# Sheet5.net
KiCad netlist of a schematic drawn in Altium Designer
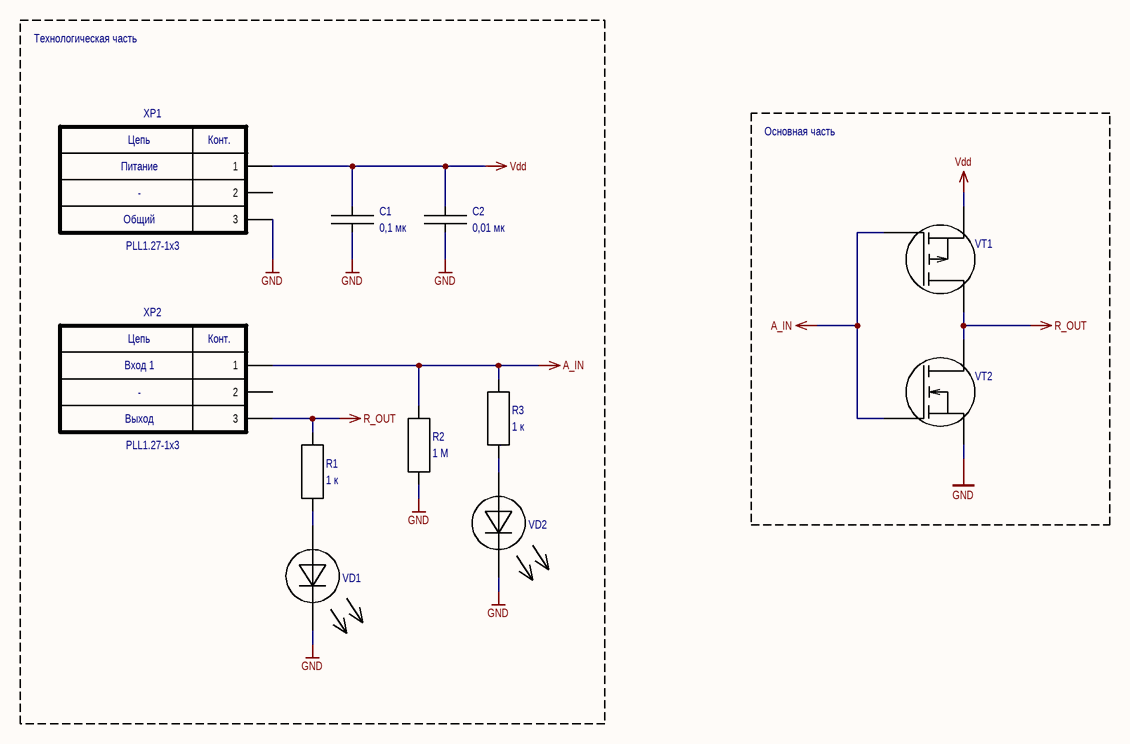
[diagram p0: Sheet5.SchDoc]

(export (version "E")
  (design (tool "Eeschema 10.0.6"))
  (components
    (comp (ref "C1")
      (value "0,1 мк")
      (footprint "K10-79_1.6_0.8(0603)")
      (fields (field (name "Comment") "0,1 мкФ ±* * * *, *"))
      (libsource (lib "IVT_LIB") (part "C - Конденсатор"))
    )
    (comp (ref "C2")
      (value "0,01 мк")
      (footprint "K10-79_1.6_0.8(0603)")
      (fields (field (name "Comment") "0,01 мкФ ±* * * *, *"))
      (libsource (lib "IVT_LIB") (part "C - Конденсатор"))
    )
    (comp (ref "R1")
      (value "1 к")
      (footprint "P1-12-0.1(0603)")
      (fields
        (field (name "PARTNUMBER") "RC0603JR-071KL")
        (field (name "TOLERANCE") "5 %")
        (field (name "Comment") "1 кОм ±5 % 0603, RC0603JR-071KL")
      )
      (libsource (lib "IVT_LIB") (part "R - Резистор"))
    )
    (comp (ref "R2")
      (value "1 М")
      (footprint "P1-12-0.1(0603)")
      (fields
        (field (name "PARTNUMBER") "RC0603JR-071KL")
        (field (name "TOLERANCE") "5 %")
        (field (name "Comment") "1 МОм ±5 % 0603, RC0603JR-071KL")
      )
      (libsource (lib "IVT_LIB") (part "R - Резистор"))
    )
    (comp (ref "R3")
      (value "1 к")
      (footprint "P1-12-0.1(0603)")
      (fields
        (field (name "PARTNUMBER") "RC0603JR-071KL")
        (field (name "TOLERANCE") "5 %")
        (field (name "Comment") "1 кОм ±5 % 0603, RC0603JR-071KL")
      )
      (libsource (lib "IVT_LIB") (part "R - Резистор"))
    )
    (comp (ref "VD1")
      (value "VD - Светодиод")
      (footprint "LED 0603")
      (fields (field (name "PARTNUMBER") "GNL-0805UBC-TL"))
      (libsource (lib "IVT_LIB") (part "VD - Светодиод"))
    )
    (comp (ref "VD2")
      (value "VD - Светодиод")
      (footprint "LED 0603")
      (fields (field (name "PARTNUMBER") "GNL-0805UBC-TL"))
      (libsource (lib "IVT_LIB") (part "VD - Светодиод"))
    )
    (comp (ref "VT1")
      (value "VT - Полевой транзистор P канал (MOSFET_P)")
      (footprint "SOT23(KT-46)")
      (description "VT")
      (libsource (lib "ALU") (part "VT - Полевой транзистор P канал (MOSFET_P)"))
    )
    (comp (ref "VT2")
      (value "VT - Полевой транзистор N канал (MOSFET_N)")
      (footprint "SOT23(KT-46)")
      (description "VT")
      (libsource (lib "ALU") (part "VT - Полевой транзистор N канал (MOSFET_N)"))
    )
    (comp (ref "XP1")
      (value "Вилка PLL1.27-1x3 RUICHI")
      (footprint "PCBComponent_1")
      (fields
        (field (name "1") "Питание")
        (field (name "3") "Общий")
        (field (name "2") "-")
        (field (name "PARTNUMBER") "PLL1.27-1x3")
      )
      (libsource (lib "IVT_LIB") (part "X - Контактное поле х3"))
    )
    (comp (ref "XP2")
      (value "KONT_POLE_POWER")
      (footprint "PCBComponent_1")
      (fields
        (field (name "1") "Вход 1")
        (field (name "2") "-")
        (field (name "3") "Выход")
        (field (name "PARTNUMBER") "PLL1.27-1x3")
      )
      (libsource (lib "IVT_LIB") (part "X - Контактное поле х3"))
    )
  )
  (nets
    (net (code "1") (name "A_IN") (class "Default")
      (node (ref "R2") (pin "1") (pinfunction "1_1") (pintype "passive"))
      (node (ref "R3") (pin "1") (pinfunction "1_1") (pintype "passive"))
      (node (ref "VT1") (pin "3") (pintype "passive"))
      (node (ref "VT2") (pin "3") (pintype "passive"))
      (node (ref "XP2") (pin "1") (pinfunction "1_1") (pintype "passive"))
    )
    (net (code "2") (name "GND") (class "Default")
      (node (ref "C1") (pin "1") (pinfunction "1_1") (pintype "passive"))
      (node (ref "C2") (pin "1") (pinfunction "1_1") (pintype "passive"))
      (node (ref "R2") (pin "2") (pinfunction "2_2") (pintype "passive"))
      (node (ref "VD1") (pin "2") (pinfunction "C_2") (pintype "passive"))
      (node (ref "VD2") (pin "2") (pinfunction "C_2") (pintype "passive"))
      (node (ref "VT2") (pin "2") (pintype "passive"))
      (node (ref "XP1") (pin "3") (pinfunction "3_3") (pintype "passive"))
    )
    (net (code "3") (name "Net-(VD1-A)") (class "Default")
      (node (ref "R1") (pin "2") (pinfunction "2_2") (pintype "passive"))
      (node (ref "VD1") (pin "1") (pinfunction "A_1") (pintype "passive"))
    )
    (net (code "4") (name "Net-(VD2-A)") (class "Default")
      (node (ref "R3") (pin "2") (pinfunction "2_2") (pintype "passive"))
      (node (ref "VD2") (pin "1") (pinfunction "A_1") (pintype "passive"))
    )
    (net (code "5") (name "R_OUT") (class "Default")
      (node (ref "R1") (pin "1") (pinfunction "1_1") (pintype "passive"))
      (node (ref "VT1") (pin "2") (pintype "passive"))
      (node (ref "VT2") (pin "1") (pintype "passive"))
      (node (ref "XP2") (pin "3") (pinfunction "3_3") (pintype "passive"))
    )
    (net (code "6") (name "Vdd") (class "Default")
      (node (ref "C1") (pin "2") (pinfunction "2_2") (pintype "passive"))
      (node (ref "C2") (pin "2") (pinfunction "2_2") (pintype "passive"))
      (node (ref "VT1") (pin "1") (pintype "passive"))
      (node (ref "XP1") (pin "1") (pinfunction "1_1") (pintype "passive"))
    )
    (net (code "7") (name "unconnected-(XP1-Pad2)") (class "Default")
      (node (ref "XP1") (pin "2") (pinfunction "2_2") (pintype "passive"))
    )
    (net (code "8") (name "unconnected-(XP2-Pad2)") (class "Default")
      (node (ref "XP2") (pin "2") (pinfunction "2_2") (pintype "passive"))
    )
  )
)
